# RasPi-BplusHAT.net
KiCad netlist of a schematic drawn in EAGLE
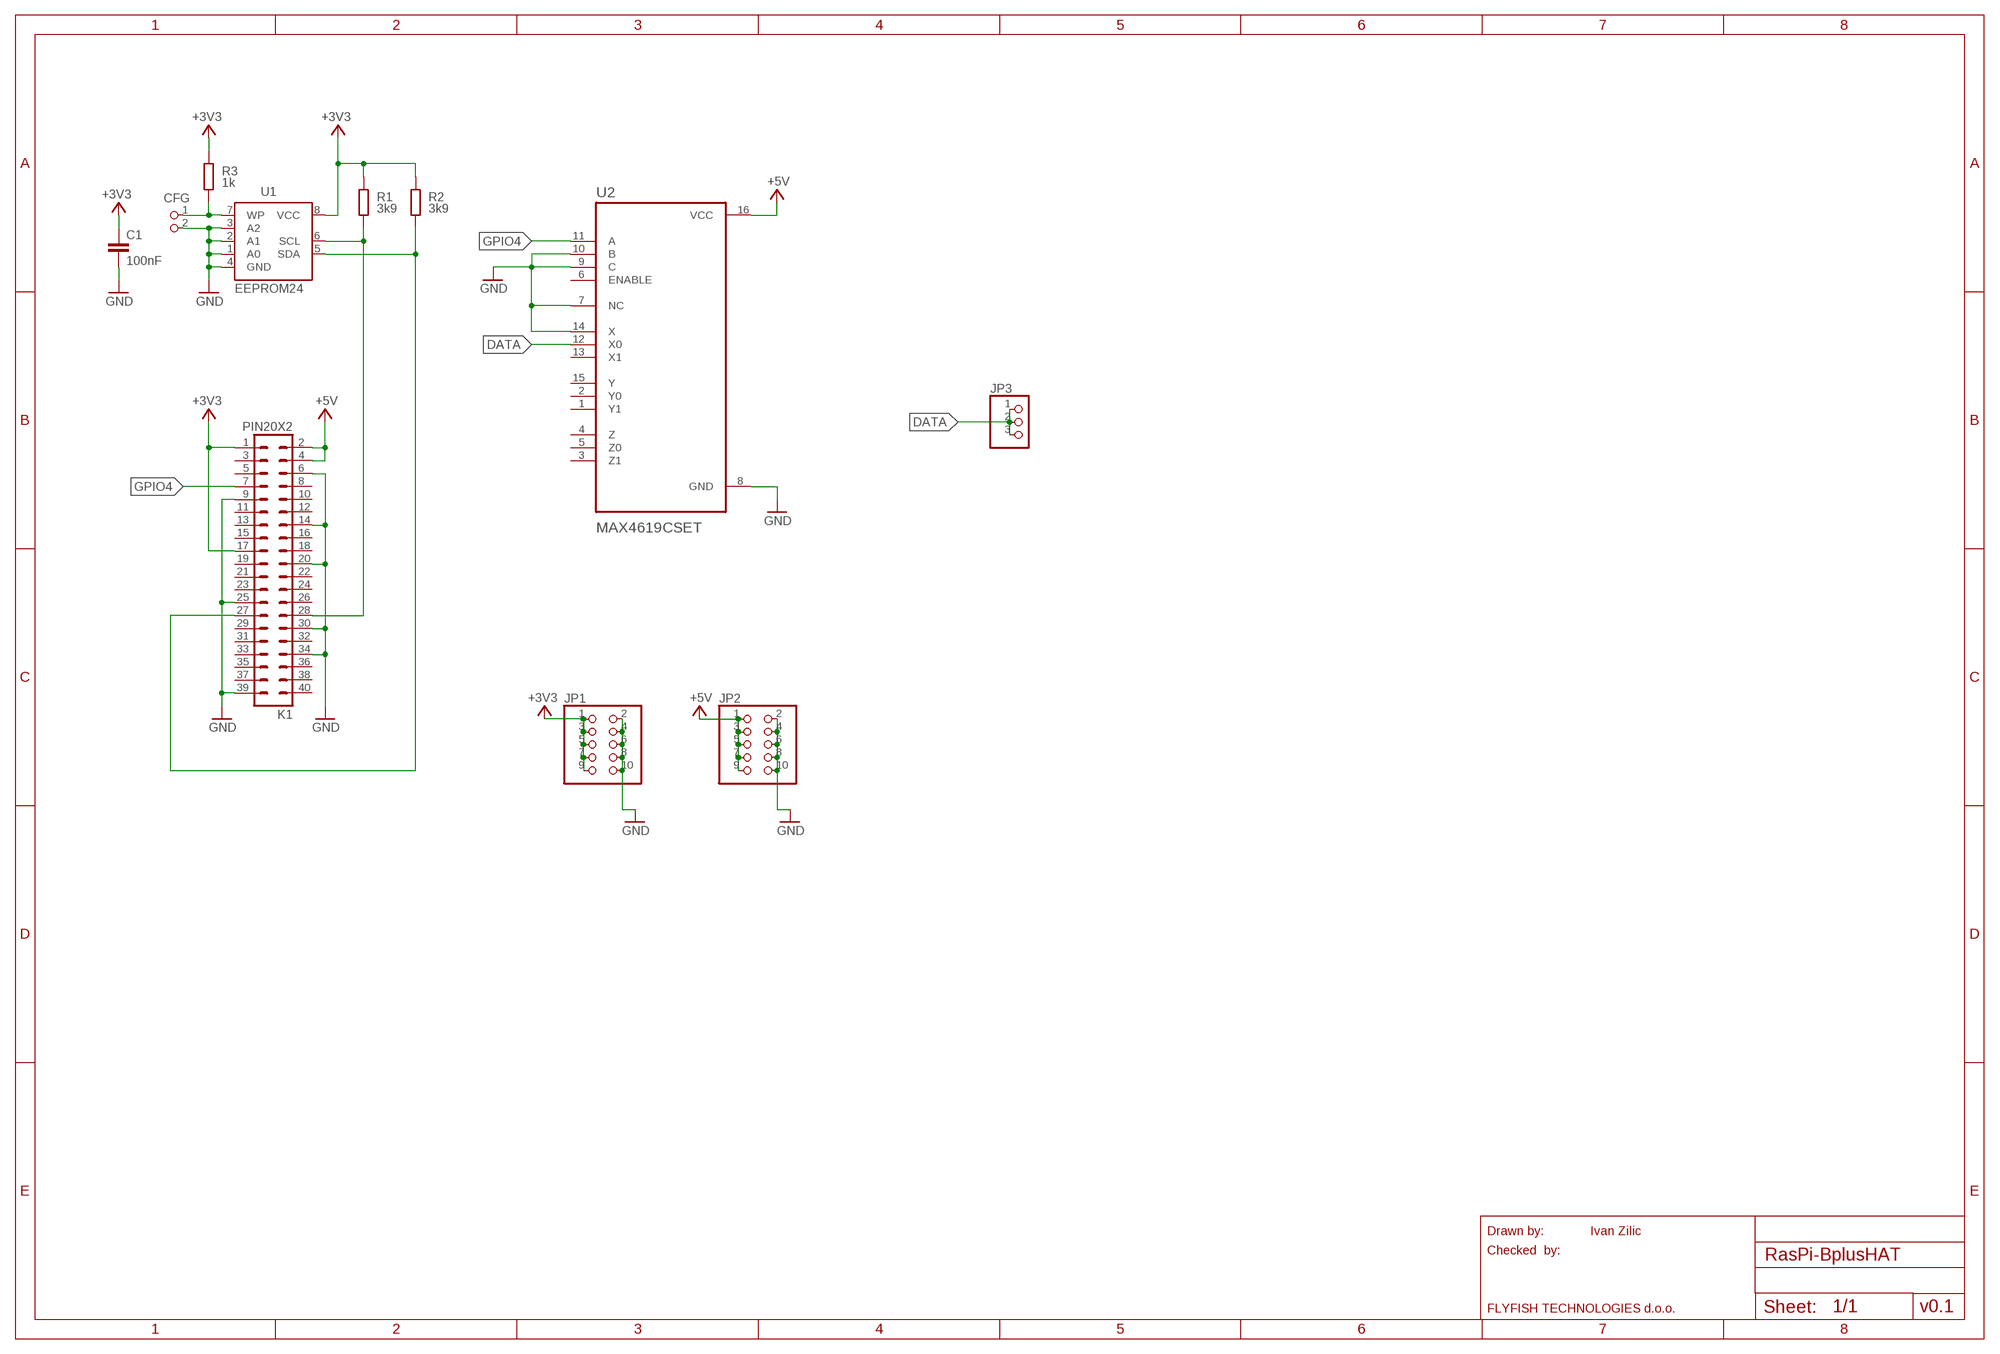
[diagram p0: schematic, sheet 1]

(export (version "E")
  (design (tool "Eeschema 10.0.6"))
  (components
    (comp (ref "C1")
      (value "100nF")
      (footprint "eagle-import:C0805K")
      (libsource (lib "eagle-import") (part "C-EUC0805K"))
    )
    (comp (ref "CFG")
      (value "PIN2_100")
      (footprint "eagle-import:PIN_W_2")
      (libsource (lib "eagle-import") (part "PIN2_100"))
    )
    (comp (ref "JP1")
      (value "PINHD-2X5")
      (footprint "eagle-import:2X05")
      (libsource (lib "eagle-import") (part "PINHD-2X5"))
    )
    (comp (ref "JP2")
      (value "PINHD-2X5")
      (footprint "eagle-import:2X05")
      (libsource (lib "eagle-import") (part "PINHD-2X5"))
    )
    (comp (ref "JP3")
      (value "PINHD-1X3")
      (footprint "eagle-import:1X03")
      (libsource (lib "eagle-import") (part "PINHD-1X3"))
    )
    (comp (ref "K1")
      (value "PIN20X2")
      (footprint "eagle-import:PIN_20X2")
      (libsource (lib "eagle-import") (part "PIN20X2"))
    )
    (comp (ref "R1")
      (value "3k9")
      (footprint "eagle-import:M0805")
      (fields (field (name "TOLERANCE") "5%"))
      (libsource (lib "eagle-import") (part "R-EU_M0805"))
    )
    (comp (ref "R2")
      (value "3k9")
      (footprint "eagle-import:M0805")
      (fields (field (name "TOLERANCE") "5%"))
      (libsource (lib "eagle-import") (part "R-EU_M0805"))
    )
    (comp (ref "R3")
      (value "1k")
      (footprint "eagle-import:M0805")
      (fields (field (name "TOLERANCE") "5%"))
      (libsource (lib "eagle-import") (part "R-EU_M0805"))
    )
    (comp (ref "U1")
      (value "EEPROM24")
      (footprint "eagle-import:SOIC8")
      (libsource (lib "eagle-import") (part "EEPROM24"))
    )
    (comp (ref "U2")
      (value "MAX4619CSET")
      (footprint "eagle-import:SOIC127P600X175-16N")
      (fields
        (field (name "DIGI-KEY_PART_NUMBER") "MAX4619CSE+T-ND")
        (field (name "MF") "Maxim Integrated")
        (field (name "MP") "MAX4619CSE+")
      )
      (libsource (lib "eagle-import") (part "MAX4619CSET"))
    )
  )
  (nets
    (net (code "1") (name "+3V3") (class "Default")
      (node (ref "C1") (pin "1") (pinfunction "1_1") (pintype "passive"))
      (node (ref "JP1") (pin "1") (pinfunction "1_1") (pintype "passive"))
      (node (ref "JP1") (pin "3") (pinfunction "3_3") (pintype "passive"))
      (node (ref "JP1") (pin "5") (pinfunction "5_5") (pintype "passive"))
      (node (ref "JP1") (pin "7") (pinfunction "7_7") (pintype "passive"))
      (node (ref "JP1") (pin "9") (pinfunction "9_9") (pintype "passive"))
      (node (ref "K1") (pin "1") (pinfunction "1_1") (pintype "passive"))
      (node (ref "K1") (pin "17") (pinfunction "17_17") (pintype "passive"))
      (node (ref "R1") (pin "2") (pinfunction "2_2") (pintype "passive"))
      (node (ref "R2") (pin "2") (pinfunction "2_2") (pintype "passive"))
      (node (ref "R3") (pin "2") (pinfunction "2_2") (pintype "passive"))
      (node (ref "U1") (pin "8") (pinfunction "VCC_8") (pintype "power_in"))
    )
    (net (code "2") (name "+5V") (class "Default")
      (node (ref "JP2") (pin "1") (pinfunction "1_1") (pintype "passive"))
      (node (ref "JP2") (pin "3") (pinfunction "3_3") (pintype "passive"))
      (node (ref "JP2") (pin "5") (pinfunction "5_5") (pintype "passive"))
      (node (ref "JP2") (pin "7") (pinfunction "7_7") (pintype "passive"))
      (node (ref "JP2") (pin "9") (pinfunction "9_9") (pintype "passive"))
      (node (ref "K1") (pin "2") (pinfunction "2_2") (pintype "passive"))
      (node (ref "K1") (pin "4") (pinfunction "4_4") (pintype "passive"))
      (node (ref "U2") (pin "16") (pinfunction "VCC_16") (pintype "power_in"))
    )
    (net (code "3") (name "DATA") (class "Default")
      (node (ref "JP3") (pin "1") (pinfunction "1_1") (pintype "passive"))
      (node (ref "JP3") (pin "2") (pinfunction "2_2") (pintype "passive"))
      (node (ref "JP3") (pin "3") (pinfunction "3_3") (pintype "passive"))
      (node (ref "U2") (pin "12") (pinfunction "X0_12") (pintype "bidirectional"))
    )
    (net (code "4") (name "GND") (class "Default")
      (node (ref "C1") (pin "2") (pinfunction "2_2") (pintype "passive"))
      (node (ref "CFG") (pin "2") (pinfunction "2_2") (pintype "passive"))
      (node (ref "JP1") (pin "10") (pinfunction "10_10") (pintype "passive"))
      (node (ref "JP1") (pin "2") (pinfunction "2_2") (pintype "passive"))
      (node (ref "JP1") (pin "4") (pinfunction "4_4") (pintype "passive"))
      (node (ref "JP1") (pin "6") (pinfunction "6_6") (pintype "passive"))
      (node (ref "JP1") (pin "8") (pinfunction "8_8") (pintype "passive"))
      (node (ref "JP2") (pin "10") (pinfunction "10_10") (pintype "passive"))
      (node (ref "JP2") (pin "2") (pinfunction "2_2") (pintype "passive"))
      (node (ref "JP2") (pin "4") (pinfunction "4_4") (pintype "passive"))
      (node (ref "JP2") (pin "6") (pinfunction "6_6") (pintype "passive"))
      (node (ref "JP2") (pin "8") (pinfunction "8_8") (pintype "passive"))
      (node (ref "K1") (pin "14") (pinfunction "14_14") (pintype "passive"))
      (node (ref "K1") (pin "20") (pinfunction "20_20") (pintype "passive"))
      (node (ref "K1") (pin "25") (pinfunction "25_25") (pintype "passive"))
      (node (ref "K1") (pin "30") (pinfunction "30_30") (pintype "passive"))
      (node (ref "K1") (pin "34") (pinfunction "34_34") (pintype "passive"))
      (node (ref "K1") (pin "39") (pinfunction "39_39") (pintype "passive"))
      (node (ref "K1") (pin "6") (pinfunction "6_6") (pintype "passive"))
      (node (ref "K1") (pin "9") (pinfunction "9_9") (pintype "passive"))
      (node (ref "U1") (pin "1") (pinfunction "A0_1") (pintype "input"))
      (node (ref "U1") (pin "2") (pinfunction "A1_2") (pintype "input"))
      (node (ref "U1") (pin "3") (pinfunction "A2_3") (pintype "input"))
      (node (ref "U1") (pin "4") (pinfunction "GND_4") (pintype "power_in"))
      (node (ref "U2") (pin "10") (pinfunction "B_10") (pintype "input"))
      (node (ref "U2") (pin "14") (pinfunction "X_14") (pintype "bidirectional"))
      (node (ref "U2") (pin "7") (pinfunction "NC_7") (pintype "bidirectional"))
      (node (ref "U2") (pin "8") (pinfunction "GND_8") (pintype "power_in"))
      (node (ref "U2") (pin "9") (pinfunction "C_9") (pintype "input"))
    )
    (net (code "5") (name "GPIO4") (class "Default")
      (node (ref "K1") (pin "7") (pinfunction "7_7") (pintype "passive"))
      (node (ref "U2") (pin "11") (pinfunction "A_11") (pintype "input"))
    )
    (net (code "6") (name "Net-(U1-SCL)") (class "Default")
      (node (ref "K1") (pin "28") (pinfunction "28_28") (pintype "passive"))
      (node (ref "R1") (pin "1") (pinfunction "1_1") (pintype "passive"))
      (node (ref "U1") (pin "6") (pinfunction "SCL_6") (pintype "input"))
    )
    (net (code "7") (name "Net-(U1-SDA)") (class "Default")
      (node (ref "K1") (pin "27") (pinfunction "27_27") (pintype "passive"))
      (node (ref "R2") (pin "1") (pinfunction "1_1") (pintype "passive"))
      (node (ref "U1") (pin "5") (pinfunction "SDA_5") (pintype "bidirectional"))
    )
    (net (code "8") (name "Net-(U1-WP)") (class "Default")
      (node (ref "CFG") (pin "1") (pinfunction "1_1") (pintype "passive"))
      (node (ref "R3") (pin "1") (pinfunction "1_1") (pintype "passive"))
      (node (ref "U1") (pin "7") (pinfunction "WP_7") (pintype "input"))
    )
    (net (code "9") (name "unconnected-(K1-Pad3)") (class "Default")
      (node (ref "K1") (pin "3") (pinfunction "3_3") (pintype "passive"))
    )
    (net (code "10") (name "unconnected-(K1-Pad5)") (class "Default")
      (node (ref "K1") (pin "5") (pinfunction "5_5") (pintype "passive"))
    )
    (net (code "11") (name "unconnected-(K1-Pad8)") (class "Default")
      (node (ref "K1") (pin "8") (pinfunction "8_8") (pintype "passive"))
    )
    (net (code "12") (name "unconnected-(K1-Pad10)") (class "Default")
      (node (ref "K1") (pin "10") (pinfunction "10_10") (pintype "passive"))
    )
    (net (code "13") (name "unconnected-(K1-Pad11)") (class "Default")
      (node (ref "K1") (pin "11") (pinfunction "11_11") (pintype "passive"))
    )
    (net (code "14") (name "unconnected-(K1-Pad12)") (class "Default")
      (node (ref "K1") (pin "12") (pinfunction "12_12") (pintype "passive"))
    )
    (net (code "15") (name "unconnected-(K1-Pad13)") (class "Default")
      (node (ref "K1") (pin "13") (pinfunction "13_13") (pintype "passive"))
    )
    (net (code "16") (name "unconnected-(K1-Pad15)") (class "Default")
      (node (ref "K1") (pin "15") (pinfunction "15_15") (pintype "passive"))
    )
    (net (code "17") (name "unconnected-(K1-Pad16)") (class "Default")
      (node (ref "K1") (pin "16") (pinfunction "16_16") (pintype "passive"))
    )
    (net (code "18") (name "unconnected-(K1-Pad18)") (class "Default")
      (node (ref "K1") (pin "18") (pinfunction "18_18") (pintype "passive"))
    )
    (net (code "19") (name "unconnected-(K1-Pad19)") (class "Default")
      (node (ref "K1") (pin "19") (pinfunction "19_19") (pintype "passive"))
    )
    (net (code "20") (name "unconnected-(K1-Pad21)") (class "Default")
      (node (ref "K1") (pin "21") (pinfunction "21_21") (pintype "passive"))
    )
    (net (code "21") (name "unconnected-(K1-Pad22)") (class "Default")
      (node (ref "K1") (pin "22") (pinfunction "22_22") (pintype "passive"))
    )
    (net (code "22") (name "unconnected-(K1-Pad23)") (class "Default")
      (node (ref "K1") (pin "23") (pinfunction "23_23") (pintype "passive"))
    )
    (net (code "23") (name "unconnected-(K1-Pad24)") (class "Default")
      (node (ref "K1") (pin "24") (pinfunction "24_24") (pintype "passive"))
    )
    (net (code "24") (name "unconnected-(K1-Pad26)") (class "Default")
      (node (ref "K1") (pin "26") (pinfunction "26_26") (pintype "passive"))
    )
    (net (code "25") (name "unconnected-(K1-Pad29)") (class "Default")
      (node (ref "K1") (pin "29") (pinfunction "29_29") (pintype "passive"))
    )
    (net (code "26") (name "unconnected-(K1-Pad31)") (class "Default")
      (node (ref "K1") (pin "31") (pinfunction "31_31") (pintype "passive"))
    )
    (net (code "27") (name "unconnected-(K1-Pad32)") (class "Default")
      (node (ref "K1") (pin "32") (pinfunction "32_32") (pintype "passive"))
    )
    (net (code "28") (name "unconnected-(K1-Pad33)") (class "Default")
      (node (ref "K1") (pin "33") (pinfunction "33_33") (pintype "passive"))
    )
    (net (code "29") (name "unconnected-(K1-Pad35)") (class "Default")
      (node (ref "K1") (pin "35") (pinfunction "35_35") (pintype "passive"))
    )
    (net (code "30") (name "unconnected-(K1-Pad36)") (class "Default")
      (node (ref "K1") (pin "36") (pinfunction "36_36") (pintype "passive"))
    )
    (net (code "31") (name "unconnected-(K1-Pad37)") (class "Default")
      (node (ref "K1") (pin "37") (pinfunction "37_37") (pintype "passive"))
    )
    (net (code "32") (name "unconnected-(K1-Pad38)") (class "Default")
      (node (ref "K1") (pin "38") (pinfunction "38_38") (pintype "passive"))
    )
    (net (code "33") (name "unconnected-(K1-Pad40)") (class "Default")
      (node (ref "K1") (pin "40") (pinfunction "40_40") (pintype "passive"))
    )
    (net (code "34") (name "unconnected-(U2-ENABLE-Pad6)") (class "Default")
      (node (ref "U2") (pin "6") (pinfunction "ENABLE_6") (pintype "input"))
    )
    (net (code "35") (name "unconnected-(U2-X1-Pad13)") (class "Default")
      (node (ref "U2") (pin "13") (pinfunction "X1_13") (pintype "bidirectional"))
    )
    (net (code "36") (name "unconnected-(U2-Y-Pad15)") (class "Default")
      (node (ref "U2") (pin "15") (pinfunction "Y_15") (pintype "bidirectional"))
    )
    (net (code "37") (name "unconnected-(U2-Y0-Pad2)") (class "Default")
      (node (ref "U2") (pin "2") (pinfunction "Y0_2") (pintype "bidirectional"))
    )
    (net (code "38") (name "unconnected-(U2-Y1-Pad1)") (class "Default")
      (node (ref "U2") (pin "1") (pinfunction "Y1_1") (pintype "bidirectional"))
    )
    (net (code "39") (name "unconnected-(U2-Z-Pad4)") (class "Default")
      (node (ref "U2") (pin "4") (pinfunction "Z_4") (pintype "bidirectional"))
    )
    (net (code "40") (name "unconnected-(U2-Z0-Pad5)") (class "Default")
      (node (ref "U2") (pin "5") (pinfunction "Z0_5") (pintype "bidirectional"))
    )
    (net (code "41") (name "unconnected-(U2-Z1-Pad3)") (class "Default")
      (node (ref "U2") (pin "3") (pinfunction "Z1_3") (pintype "bidirectional"))
    )
  )
)
